# Schema_rechtsonder.net
KiCad netlist of a schematic drawn in Altium Designer
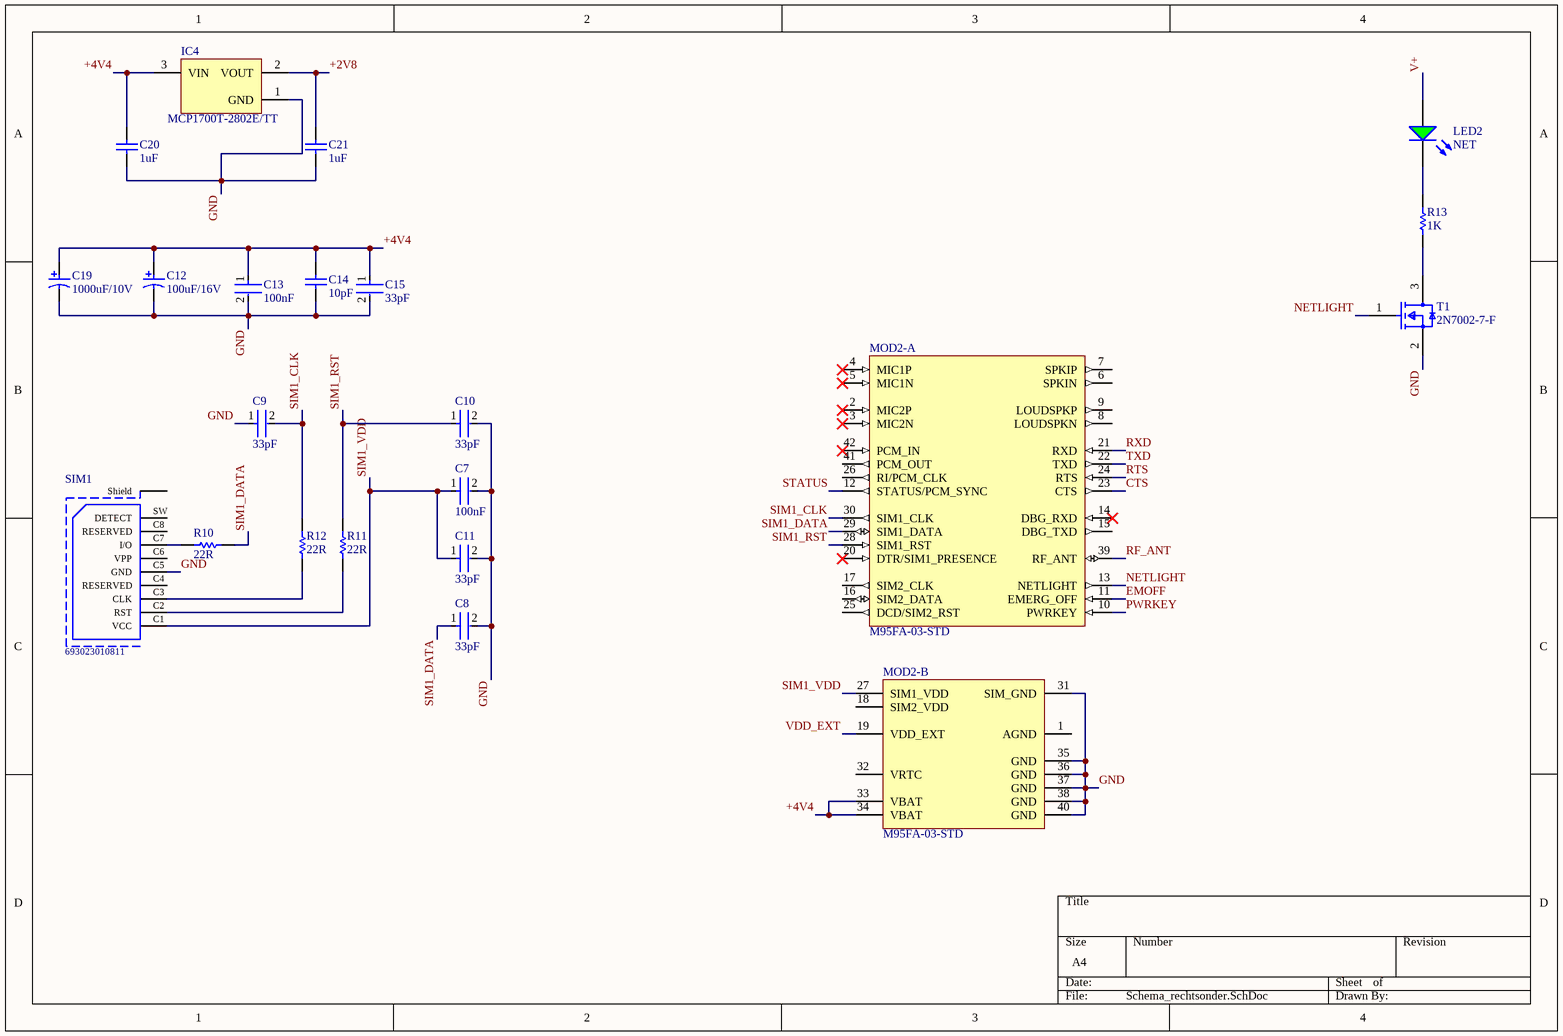
[diagram p0: Schema_rechtsonder.SchDoc]

(export (version "E")
  (design (tool "Eeschema 10.0.6"))
  (components
    (comp (ref "C7")
      (value "100nF")
      (footprint "FP-CC1206-1_25-MFG")
      (description "CAP CER 0.1UF 50V X7R 1206")
      (fields
        (field (name "OCTOPART") "https://octopart.com/cc1206krx7r9bb104-yageo-39467816")
        (field (name "TOLERANCE") "0.1")
      )
      (libsource (lib "Altium Content Vault") (part "11868f565c42a9108669ba33697ecf6"))
    )
    (comp (ref "C8")
      (value "33pF")
      (footprint "FP-C0805C-DN-MFG")
      (description "CAP CER 33PF 50V 1% NP0 0805")
      (fields (field (name "MANUFACTURER PART NUMBER") "C0805C330F5GACTU") (field (name "TOLERANCE") "0.01"))
      (libsource (lib "Altium Content Vault") (part "b4654b650e69147ec39a6b967a45e02"))
    )
    (comp (ref "C9")
      (value "33pF")
      (footprint "FP-C0805C-DN-MFG")
      (description "CAP CER 33PF 50V 1% NP0 0805")
      (fields (field (name "MANUFACTURER PART NUMBER") "C0805C330F5GACTU") (field (name "TOLERANCE") "0.01"))
      (libsource (lib "Altium Content Vault") (part "b4654b650e69147ec39a6b967a45e02"))
    )
    (comp (ref "C10")
      (value "33pF")
      (footprint "FP-C0805C-DN-MFG")
      (description "CAP CER 33PF 50V 1% NP0 0805")
      (fields (field (name "MANUFACTURER PART NUMBER") "C0805C330F5GACTU") (field (name "TOLERANCE") "0.01"))
      (libsource (lib "Altium Content Vault") (part "b4654b650e69147ec39a6b967a45e02"))
    )
    (comp (ref "C11")
      (value "33pF")
      (footprint "FP-C0805C-DN-MFG")
      (description "CAP CER 33PF 50V 1% NP0 0805")
      (fields (field (name "MANUFACTURER PART NUMBER") "C0805C330F5GACTU") (field (name "TOLERANCE") "0.01"))
      (libsource (lib "Altium Content Vault") (part "b4654b650e69147ec39a6b967a45e02"))
    )
    (comp (ref "C12")
      (value "100uF/16V")
      (footprint "AVX-TAJ-C-2_M")
      (description "Standard Tantalum, 100 uF, +/- 10%, 16 V, -55 to 125 degC, 2-Pin SMD (2312), RoHS, Tape and Reel")
      (fields (field (name "TOLERANCE") "10%") (field (name "MANUFACTURER") "AVX"))
      (libsource (lib "Altium Content Vault") (part "CAP-P-2"))
    )
    (comp (ref "C13")
      (value "100nF")
      (footprint "FP-CC1206-1_25-MFG")
      (description "CAP CER 0.1UF 50V X7R 1206")
      (fields
        (field (name "OCTOPART") "https://octopart.com/cc1206krx7r9bb104-yageo-39467816")
        (field (name "TOLERANCE") "0.1")
      )
      (libsource (lib "Altium Content Vault") (part "11868f565c42a9108669ba33697ecf6"))
    )
    (comp (ref "C14")
      (value "10pF")
      (footprint "CAPC2013X145X50ML20T20")
      (fields (field (name "MANUFACTURER") "Vitramon") (field (name "PART NUMBER") "VJ0805A100FXACW1BC"))
      (libsource (lib "Altium Content Vault") (part "CAP"))
    )
    (comp (ref "C15")
      (value "33pF")
      (footprint "FP-C0805C-DN-MFG")
      (description "CAP CER 33PF 50V 1% NP0 0805")
      (fields (field (name "MANUFACTURER PART NUMBER") "C0805C330F5GACTU") (field (name "TOLERANCE") "0.01"))
      (libsource (lib "Altium Content Vault") (part "b4654b650e69147ec39a6b967a45e02"))
    )
    (comp (ref "C19")
      (value "1000uF/10V")
      (footprint "NIC-CAPA2-10X10_V")
      (fields (field (name "MANUFACTURER") "Nichicon") (field (name "PARTNUMBER") "UUD1A102MNL1GS"))
      (libsource (lib "Altium Content Vault") (part "NIC-CAP-P-2"))
    )
    (comp (ref "C20")
      (value "1uF")
      (footprint "CAPC1206(3216)130_M")
      (description "CAP 1uF 10V ±10% 1206 (3216 Metric) Thickness 1.3mm SMD")
      (fields (field (name "TOLERANCE") "Â±10%"))
      (libsource (lib "Altium Content Vault") (part "CAP"))
    )
    (comp (ref "C21")
      (value "1uF")
      (footprint "CAPC1206(3216)130_M")
      (description "CAP 1uF 10V ±10% 1206 (3216 Metric) Thickness 1.3mm SMD")
      (fields (field (name "TOLERANCE") "Â±10%"))
      (libsource (lib "Altium Content Vault") (part "CAP"))
    )
    (comp (ref "IC4")
      (value "MCP1700T-2802E/TT")
      (footprint "SOT-23-TT3_M")
      (description "Low Quiescent Current LDO, 3-Pin SOT-23, Extended Temperature, Tape and Reel")
      (libsource (lib "Altium Content Vault") (part "PM-LINEREG-MCP1700-IL3"))
    )
    (comp (ref "LED2")
      (value "NET")
      (footprint "LUMX-SML-LX1206GC-TR_V")
      (description "Green Led, Water Clear Lens, 10 mcd, 565 nm, 2.2 V, -40 to 85 degC, 2-Pin SMD, RoHS, Tape and Reel")
      (fields (field (name "PART NO") "SML-LX1206GC-TR") (field (name "MANUFACTURER") "Lumex"))
      (libsource (lib "Altium Content Vault") (part "LED-GREEN-AK-2"))
    )
    (comp (ref "MOD2-")
      (value "M95FA-03-STD")
      (footprint "QUEC-M95FA-03-STD_V")
      (fields (field (name "MANUFACTURER") "QUECTELWIRELESSSOLUTIONS"))
      (libsource (lib "Altium Content Vault") (part "QUEC-M95FA-03-STD"))
    )
    (comp (ref "R10")
      (value "22R")
      (footprint "RESC3225X60X45ML20T20")
      (fields (field (name "MANUFACTURER") "Vishay Dale") (field (name "PART NUMBER") "CRCW121024R9FKEA"))
      (libsource (lib "Altium Content Vault") (part "RES"))
    )
    (comp (ref "R11")
      (value "22R")
      (footprint "RESC3225X60X45ML20T20")
      (fields (field (name "MANUFACTURER") "Vishay Dale") (field (name "PART NUMBER") "CRCW121024R9FKEA"))
      (libsource (lib "Altium Content Vault") (part "RES"))
    )
    (comp (ref "R12")
      (value "22R")
      (footprint "RESC3225X60X45ML20T20")
      (fields (field (name "MANUFACTURER") "Vishay Dale") (field (name "PART NUMBER") "CRCW121024R9FKEA"))
      (libsource (lib "Altium Content Vault") (part "RES"))
    )
    (comp (ref "R13")
      (value "1K")
      (footprint "RESC3225X60X45ML20T20")
      (fields (field (name "MANUFACTURER") "Vishay Dale") (field (name "PART NUMBER") "CRCW121024R9FKEA"))
      (libsource (lib "Altium Content Vault") (part "RES"))
    )
    (comp (ref "SIM1")
      (value "693023010811")
      (footprint "693023010811")
      (description "WR-CRD Micro SIM Card Connector, Push & Pull, with Card Detection")
      (fields (field (name "MANUFACTURER") "Wurth Elektronik") (field (name "PUBLISHER") "WurthElektronik"))
      (libsource (lib "Altium Content Vault") (part "WE-CN-SD-8-1SW-1S"))
    )
    (comp (ref "T1")
      (value "2N7002-7-F")
      (footprint "FP-SOT23-MFG")
      (description "MOSFET N-CH 60V 115MA SOT23-3")
      (fields (field (name "VOLTAGE") "60V"))
      (libsource (lib "Altium Content Vault") (part "3b9c635fedb024a5347a57b145af9cc"))
    )
  )
  (nets
    (net (code "1") (name "/+2V8") (class "Default")
      (node (ref "C21") (pin "2") (pinfunction "2_2") (pintype "passive"))
      (node (ref "IC4") (pin "2") (pinfunction "VOUT_2") (pintype "power_in"))
    )
    (net (code "2") (name "/+4V4") (class "Default")
      (node (ref "C12") (pin "1") (pinfunction "1_1") (pintype "passive"))
      (node (ref "C13") (pin "1") (pinfunction "1_1") (pintype "passive"))
      (node (ref "C14") (pin "2") (pinfunction "2_2") (pintype "passive"))
      (node (ref "C15") (pin "1") (pinfunction "1_1") (pintype "passive"))
      (node (ref "C19") (pin "1") (pinfunction "1_1") (pintype "passive"))
      (node (ref "C20") (pin "2") (pinfunction "2_2") (pintype "passive"))
      (node (ref "IC4") (pin "3") (pinfunction "VIN_3") (pintype "power_in"))
      (node (ref "MOD2-") (pin "33") (pinfunction "VBAT_33") (pintype "power_in"))
      (node (ref "MOD2-") (pin "34") (pinfunction "VBAT_34") (pintype "power_in"))
    )
    (net (code "3") (name "/CTS") (class "Default")
      (node (ref "MOD2-") (pin "23") (pinfunction "CTS_23") (pintype "output"))
    )
    (net (code "4") (name "/EMOFF") (class "Default")
      (node (ref "MOD2-") (pin "11") (pinfunction "EMERG_OFF_11") (pintype "input"))
    )
    (net (code "5") (name "/GND") (class "Default")
      (node (ref "C10") (pin "2") (pinfunction "2_2") (pintype "passive"))
      (node (ref "C11") (pin "2") (pinfunction "2_2") (pintype "passive"))
      (node (ref "C12") (pin "2") (pinfunction "2_2") (pintype "passive"))
      (node (ref "C13") (pin "2") (pinfunction "2_2") (pintype "passive"))
      (node (ref "C14") (pin "1") (pinfunction "1_1") (pintype "passive"))
      (node (ref "C15") (pin "2") (pinfunction "2_2") (pintype "passive"))
      (node (ref "C19") (pin "2") (pinfunction "2_2") (pintype "passive"))
      (node (ref "C20") (pin "1") (pinfunction "1_1") (pintype "passive"))
      (node (ref "C21") (pin "1") (pinfunction "1_1") (pintype "passive"))
      (node (ref "C7") (pin "2") (pinfunction "2_2") (pintype "passive"))
      (node (ref "C8") (pin "2") (pinfunction "2_2") (pintype "passive"))
      (node (ref "C9") (pin "1") (pinfunction "1_1") (pintype "passive"))
      (node (ref "IC4") (pin "1") (pinfunction "GND_1") (pintype "power_in"))
      (node (ref "MOD2-") (pin "31") (pinfunction "SIM_GND_31") (pintype "power_in"))
      (node (ref "MOD2-") (pin "35") (pinfunction "GND_35") (pintype "power_in"))
      (node (ref "MOD2-") (pin "36") (pinfunction "GND_36") (pintype "power_in"))
      (node (ref "MOD2-") (pin "37") (pinfunction "GND_37") (pintype "power_in"))
      (node (ref "MOD2-") (pin "38") (pinfunction "GND_38") (pintype "power_in"))
      (node (ref "MOD2-") (pin "40") (pinfunction "GND_40") (pintype "power_in"))
      (node (ref "SIM1") (pin "C5") (pinfunction "GND_C5") (pintype "passive"))
      (node (ref "T1") (pin "2") (pinfunction "S_2") (pintype "passive"))
    )
    (net (code "6") (name "/NETLIGHT") (class "Default")
      (node (ref "MOD2-") (pin "13") (pinfunction "NETLIGHT_13") (pintype "output"))
      (node (ref "T1") (pin "1") (pinfunction "G_1") (pintype "passive"))
    )
    (net (code "7") (name "/PWRKEY") (class "Default")
      (node (ref "MOD2-") (pin "10") (pinfunction "PWRKEY_10") (pintype "input"))
    )
    (net (code "8") (name "/RF_ANT") (class "Default")
      (node (ref "MOD2-") (pin "39") (pinfunction "RF_ANT_39") (pintype "bidirectional"))
    )
    (net (code "9") (name "/RTS") (class "Default")
      (node (ref "MOD2-") (pin "24") (pinfunction "RTS_24") (pintype "input"))
    )
    (net (code "10") (name "/RXD") (class "Default")
      (node (ref "MOD2-") (pin "21") (pinfunction "RXD_21") (pintype "input"))
    )
    (net (code "11") (name "/SIM1_CLK") (class "Default")
      (node (ref "C9") (pin "2") (pinfunction "2_2") (pintype "passive"))
      (node (ref "MOD2-") (pin "30") (pinfunction "SIM1_CLK_30") (pintype "output"))
      (node (ref "R12") (pin "2") (pinfunction "2_2") (pintype "passive"))
    )
    (net (code "12") (name "/SIM1_DATA") (class "Default")
      (node (ref "C8") (pin "1") (pinfunction "1_1") (pintype "passive"))
      (node (ref "MOD2-") (pin "29") (pinfunction "SIM1_DATA_29") (pintype "bidirectional"))
      (node (ref "R10") (pin "1") (pinfunction "1_1") (pintype "passive"))
    )
    (net (code "13") (name "/SIM1_RST") (class "Default")
      (node (ref "C10") (pin "1") (pinfunction "1_1") (pintype "passive"))
      (node (ref "MOD2-") (pin "28") (pinfunction "SIM1_RST_28") (pintype "input"))
      (node (ref "R11") (pin "2") (pinfunction "2_2") (pintype "passive"))
    )
    (net (code "14") (name "/SIM1_VDD") (class "Default")
      (node (ref "C11") (pin "1") (pinfunction "1_1") (pintype "passive"))
      (node (ref "C7") (pin "1") (pinfunction "1_1") (pintype "passive"))
      (node (ref "MOD2-") (pin "27") (pinfunction "SIM1_VDD_27") (pintype "power_in"))
      (node (ref "SIM1") (pin "C1") (pinfunction "VCC_C1") (pintype "passive"))
    )
    (net (code "15") (name "/STATUS") (class "Default")
      (node (ref "MOD2-") (pin "12") (pinfunction "STATUS/PCM_SYNC_12") (pintype "output"))
    )
    (net (code "16") (name "/TXD") (class "Default")
      (node (ref "MOD2-") (pin "22") (pinfunction "TXD_22") (pintype "output"))
    )
    (net (code "17") (name "/V+") (class "Default")
      (node (ref "LED2") (pin "1") (pinfunction "A_1") (pintype "passive"))
    )
    (net (code "18") (name "/VDD_EXT") (class "Default")
      (node (ref "MOD2-") (pin "19") (pinfunction "VDD_EXT_19") (pintype "power_in"))
    )
    (net (code "19") (name "Net-(LED2-K)") (class "Default")
      (node (ref "LED2") (pin "2") (pinfunction "K_2") (pintype "passive"))
      (node (ref "R13") (pin "2") (pinfunction "2_2") (pintype "passive"))
    )
    (net (code "20") (name "Net-(SIM1-CLK)") (class "Default")
      (node (ref "R12") (pin "1") (pinfunction "1_1") (pintype "passive"))
      (node (ref "SIM1") (pin "C3") (pinfunction "CLK_C3") (pintype "passive"))
    )
    (net (code "21") (name "Net-(SIM1-I{slash}O)") (class "Default")
      (node (ref "R10") (pin "2") (pinfunction "2_2") (pintype "passive"))
      (node (ref "SIM1") (pin "C7") (pinfunction "I/O_C7") (pintype "passive"))
    )
    (net (code "22") (name "Net-(SIM1-RST)") (class "Default")
      (node (ref "R11") (pin "1") (pinfunction "1_1") (pintype "passive"))
      (node (ref "SIM1") (pin "C2") (pinfunction "RST_C2") (pintype "passive"))
    )
    (net (code "23") (name "Net-(T1-D)") (class "Default")
      (node (ref "R13") (pin "1") (pinfunction "1_1") (pintype "passive"))
      (node (ref "T1") (pin "3") (pinfunction "D_3") (pintype "passive"))
    )
    (net (code "24") (name "unconnected-(MOD2-A-DBG_RXD-Pad14)") (class "Default")
      (node (ref "MOD2-") (pin "14") (pinfunction "DBG_RXD_14") (pintype "input+no_connect"))
    )
    (net (code "25") (name "unconnected-(MOD2-A-DBG_TXD-Pad15)") (class "Default")
      (node (ref "MOD2-") (pin "15") (pinfunction "DBG_TXD_15") (pintype "output"))
    )
    (net (code "26") (name "unconnected-(MOD2-A-DCD{slash}SIM2_RST-Pad25)") (class "Default")
      (node (ref "MOD2-") (pin "25") (pinfunction "DCD/SIM2_RST_25") (pintype "output"))
    )
    (net (code "27") (name "unconnected-(MOD2-A-DTR{slash}SIM1_PRESENCE-Pad20)") (class "Default")
      (node (ref "MOD2-") (pin "20") (pinfunction "DTR/SIM1_PRESENCE_20") (pintype "input+no_connect"))
    )
    (net (code "28") (name "unconnected-(MOD2-A-LOUDSPKN-Pad8)") (class "Default")
      (node (ref "MOD2-") (pin "8") (pinfunction "LOUDSPKN_8") (pintype "output"))
    )
    (net (code "29") (name "unconnected-(MOD2-A-LOUDSPKP-Pad9)") (class "Default")
      (node (ref "MOD2-") (pin "9") (pinfunction "LOUDSPKP_9") (pintype "output"))
    )
    (net (code "30") (name "unconnected-(MOD2-A-MIC1N-Pad5)") (class "Default")
      (node (ref "MOD2-") (pin "5") (pinfunction "MIC1N_5") (pintype "input+no_connect"))
    )
    (net (code "31") (name "unconnected-(MOD2-A-MIC1P-Pad4)") (class "Default")
      (node (ref "MOD2-") (pin "4") (pinfunction "MIC1P_4") (pintype "input+no_connect"))
    )
    (net (code "32") (name "unconnected-(MOD2-A-MIC2N-Pad3)") (class "Default")
      (node (ref "MOD2-") (pin "3") (pinfunction "MIC2N_3") (pintype "input+no_connect"))
    )
    (net (code "33") (name "unconnected-(MOD2-A-MIC2P-Pad2)") (class "Default")
      (node (ref "MOD2-") (pin "2") (pinfunction "MIC2P_2") (pintype "input+no_connect"))
    )
    (net (code "34") (name "unconnected-(MOD2-A-PCM_IN-Pad42)") (class "Default")
      (node (ref "MOD2-") (pin "42") (pinfunction "PCM_IN_42") (pintype "input+no_connect"))
    )
    (net (code "35") (name "unconnected-(MOD2-A-PCM_OUT-Pad41)") (class "Default")
      (node (ref "MOD2-") (pin "41") (pinfunction "PCM_OUT_41") (pintype "output"))
    )
    (net (code "36") (name "unconnected-(MOD2-A-RI{slash}PCM_CLK-Pad26)") (class "Default")
      (node (ref "MOD2-") (pin "26") (pinfunction "RI/PCM_CLK_26") (pintype "output"))
    )
    (net (code "37") (name "unconnected-(MOD2-A-SIM2_CLK-Pad17)") (class "Default")
      (node (ref "MOD2-") (pin "17") (pinfunction "SIM2_CLK_17") (pintype "output"))
    )
    (net (code "38") (name "unconnected-(MOD2-A-SIM2_DATA-Pad16)") (class "Default")
      (node (ref "MOD2-") (pin "16") (pinfunction "SIM2_DATA_16") (pintype "bidirectional"))
    )
    (net (code "39") (name "unconnected-(MOD2-A-SPKIN-Pad6)") (class "Default")
      (node (ref "MOD2-") (pin "6") (pinfunction "SPKIN_6") (pintype "output"))
    )
    (net (code "40") (name "unconnected-(MOD2-A-SPKIP-Pad7)") (class "Default")
      (node (ref "MOD2-") (pin "7") (pinfunction "SPKIP_7") (pintype "output"))
    )
    (net (code "41") (name "unconnected-(MOD2-B-AGND-Pad1)") (class "Default")
      (node (ref "MOD2-") (pin "1") (pinfunction "AGND_1") (pintype "power_in"))
    )
    (net (code "42") (name "unconnected-(MOD2-B-SIM2_VDD-Pad18)") (class "Default")
      (node (ref "MOD2-") (pin "18") (pinfunction "SIM2_VDD_18") (pintype "power_in"))
    )
    (net (code "43") (name "unconnected-(MOD2-B-VRTC-Pad32)") (class "Default")
      (node (ref "MOD2-") (pin "32") (pinfunction "VRTC_32") (pintype "power_in"))
    )
    (net (code "44") (name "unconnected-(SIM1-DETECT-PadSW)") (class "Default")
      (node (ref "SIM1") (pin "SW") (pinfunction "DETECT_SW") (pintype "passive"))
    )
    (net (code "45") (name "unconnected-(SIM1-PadShield)") (class "Default")
      (node (ref "SIM1") (pin "Shield") (pinfunction "Shield_Shield") (pintype "passive"))
    )
    (net (code "46") (name "unconnected-(SIM1-RESERVED-PadC4)") (class "Default")
      (node (ref "SIM1") (pin "C4") (pinfunction "RESERVED_C4") (pintype "passive"))
    )
    (net (code "47") (name "unconnected-(SIM1-RESERVED-PadC8)") (class "Default")
      (node (ref "SIM1") (pin "C8") (pinfunction "RESERVED_C8") (pintype "passive"))
    )
    (net (code "48") (name "unconnected-(SIM1-VPP-PadC6)") (class "Default")
      (node (ref "SIM1") (pin "C6") (pinfunction "VPP_C6") (pintype "passive"))
    )
  )
)
